# sheet3_nRF52832.net
KiCad netlist of a schematic drawn in Altium Designer
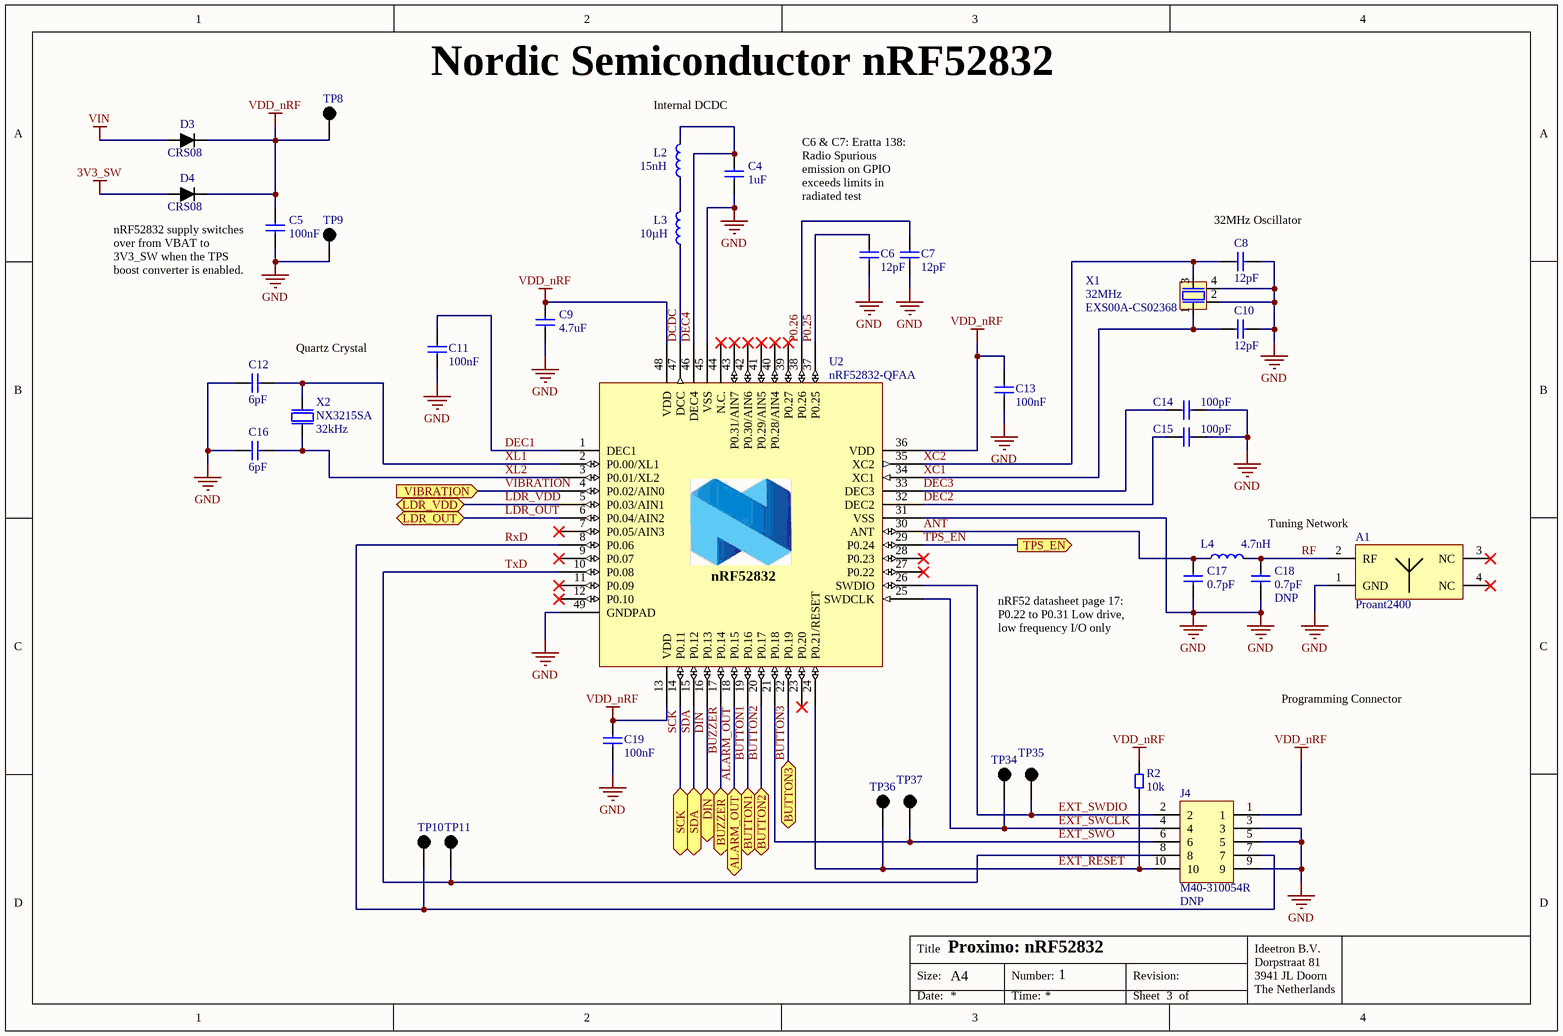
[diagram p0: sheet3_nRF52832.SchDoc]

(export (version "E")
  (design (tool "Eeschema 10.0.6"))
  (components
    (comp (ref "A1")
      (value "Proant2400")
      (footprint "Proant2400")
      (description "Onboard SMD 2400 MHz Antenna for BLE, WLAN/Wifi")
      (fields (field (name "MANUFACTURER") "Proant") (field (name "MANUFACTURER PART NUMBER") "PRO-OB-440"))
      (libsource (lib "Schlib") (part "Proant2400"))
    )
    (comp (ref "C4")
      (value "1uF")
      (footprint "CAP0603_GR18_MURATA")
      (description "Capacitor 1uF X5R 0603 Murata")
      (fields
        (field (name "MANUFACTURER") "Murata")
        (field (name "MANUFACTURER PART NUMBER") "GRM188R61E105KA12D")
      )
      (libsource (lib "Schlib") (part "CAP_0603_1uF"))
    )
    (comp (ref "C5")
      (value "100nF")
      (footprint "CAP0603_GCx18_MURATA")
      (description "Capacitor 0603 100nF")
      (fields
        (field (name "MANUFACTURER") "Murata")
        (field (name "MANUFACTURER PART NUMBER") "GCJ188R71C104KA01D")
      )
      (libsource (lib "Schlib") (part "CAP_0603_100nF"))
    )
    (comp (ref "C6")
      (value "12pF")
      (footprint "CAP0402_GCx15_Murata")
      (description "Capacitor NP0 0402")
      (fields
        (field (name "MANUFACTURER") "Murata")
        (field (name "MANUFACTURER PART NUMBER") "GCM1555C1H120JA16D")
      )
      (libsource (lib "Schlib") (part "CAP_0402_12pF"))
    )
    (comp (ref "C7")
      (value "12pF")
      (footprint "CAP0402_GCx15_Murata")
      (description "Capacitor NP0 0402")
      (fields
        (field (name "MANUFACTURER") "Murata")
        (field (name "MANUFACTURER PART NUMBER") "GCM1555C1H120JA16D")
      )
      (libsource (lib "Schlib") (part "CAP_0402_12pF"))
    )
    (comp (ref "C8")
      (value "12pF")
      (footprint "CAP0402_GCx15_Murata")
      (description "Capacitor NP0 0402")
      (fields
        (field (name "MANUFACTURER") "Murata")
        (field (name "MANUFACTURER PART NUMBER") "GCM1555C1H120JA16D")
      )
      (libsource (lib "Schlib") (part "CAP_0402_12pF"))
    )
    (comp (ref "C9")
      (value "4.7uF")
      (footprint "CAP0603_GR18_MURATA")
      (description "Capacitor X5R 0603 Murata")
      (fields
        (field (name "MANUFACTURER") "Murata")
        (field (name "MANUFACTURER PART NUMBER") "GRM188R60J475KE19D")
      )
      (libsource (lib "Schlib") (part "CAP_0603_4u7"))
    )
    (comp (ref "C10")
      (value "12pF")
      (footprint "CAP0402_GCx15_Murata")
      (description "Capacitor NP0 0402")
      (fields
        (field (name "MANUFACTURER") "Murata")
        (field (name "MANUFACTURER PART NUMBER") "GCM1555C1H120JA16D")
      )
      (libsource (lib "Schlib") (part "CAP_0402_12pF"))
    )
    (comp (ref "C11")
      (value "100nF")
      (footprint "CAP0603_GCx18_MURATA")
      (description "Capacitor 0603 100nF")
      (fields
        (field (name "MANUFACTURER") "Murata")
        (field (name "MANUFACTURER PART NUMBER") "GCJ188R71C104KA01D")
      )
      (libsource (lib "Schlib") (part "CAP_0603_100nF"))
    )
    (comp (ref "C12")
      (value "6pF")
      (footprint "CAP0603_GCx18_MURATA")
      (description "Capacitor NP0 0603 50V")
      (fields (field (name "PART NUMBER") "GCM1885C1H6R0CA16D") (field (name "MANUFACTURER") "Murata"))
      (libsource (lib "Schlib") (part "CAP_0603_6pF"))
    )
    (comp (ref "C13")
      (value "100nF")
      (footprint "CAP0603_GCx18_MURATA")
      (description "Capacitor 0603 100nF")
      (fields
        (field (name "MANUFACTURER") "Murata")
        (field (name "MANUFACTURER PART NUMBER") "GCJ188R71C104KA01D")
      )
      (libsource (lib "Schlib") (part "CAP_0603_100nF"))
    )
    (comp (ref "C14")
      (value "100pF")
      (footprint "CAP0603_GCx18_MURATA")
      (description "Capacitor 100pF 0603 NP0")
      (fields
        (field (name "MANUFACTURER") "Murata")
        (field (name "MANUFACTURER PART NUMBER") "GCM1885C1H101JA16D")
      )
      (libsource (lib "Schlib") (part "CAP_0603_100pF"))
    )
    (comp (ref "C15")
      (value "100pF")
      (footprint "CAP0603_GCx18_MURATA")
      (description "Capacitor 100pF 0603 NP0")
      (fields
        (field (name "MANUFACTURER") "Murata")
        (field (name "MANUFACTURER PART NUMBER") "GCM1885C1H101JA16D")
      )
      (libsource (lib "Schlib") (part "CAP_0603_100pF"))
    )
    (comp (ref "C16")
      (value "6pF")
      (footprint "CAP0603_GCx18_MURATA")
      (description "Capacitor NP0 0603 50V")
      (fields (field (name "PART NUMBER") "GCM1885C1H6R0CA16D") (field (name "MANUFACTURER") "Murata"))
      (libsource (lib "Schlib") (part "CAP_0603_6pF"))
    )
    (comp (ref "C17")
      (value "0.7pF")
      (footprint "CAP0402 Johansen Technology")
      (description "Capacitor 0.7pF 0402")
      (fields
        (field (name "MANUFACTURER") "Johansen Technology")
        (field (name "MANUFACTURER PART NUMBER") "500R07S0R7AV4T")
      )
      (libsource (lib "Schlib") (part "CAP_0402_0p7F"))
    )
    (comp (ref "C18")
      (value "0.7pF")
      (footprint "CAP0402 Johansen Technology")
      (description "Capacitor 0.7pF 0402")
      (fields (field (name "MANUFACTURER PART NUMBER") "500R07S0R7AV4T") (field (name "REMARK") "DNP"))
      (libsource (lib "Schlib") (part "CAP_0402_0p7F"))
    )
    (comp (ref "C19")
      (value "100nF")
      (footprint "CAP0603_GCx18_MURATA")
      (description "Capacitor 0603 100nF")
      (fields
        (field (name "MANUFACTURER") "Murata")
        (field (name "MANUFACTURER PART NUMBER") "GCJ188R71C104KA01D")
      )
      (libsource (lib "Schlib") (part "CAP_0603_100nF"))
    )
    (comp (ref "D3")
      (value "CRS08")
      (footprint "SOD-123F")
      (description "CRS08 Schottky Diode")
      (fields (field (name "MANUFACTURER") "Tohsiba"))
      (libsource (lib "Schlib") (part "CRS08 Schottky Diode"))
    )
    (comp (ref "D4")
      (value "CRS08")
      (footprint "SOD-123F")
      (description "CRS08 Schottky Diode")
      (fields (field (name "MANUFACTURER") "Tohsiba"))
      (libsource (lib "Schlib") (part "CRS08 Schottky Diode"))
    )
    (comp (ref "J4")
      (value "M40-310054R")
      (footprint "Harwin connector")
      (description "Harwin connector 2Rows x 6 contacts M40-3100545R")
      (fields (field (name "MANUFACTURER") "Harwin") (field (name "REMARK") "DNP"))
      (libsource (lib "Schlib") (part "Harwin Connector"))
    )
    (comp (ref "L2")
      (value "15nH")
      (footprint "WE-MK_0402A")
      (description "WE-MK Multilayer Ceramic SMD Inductor, size 0402A, 15nH")
      (fields
        (field (name "PARTNUMBER") "744784115A")
        (field (name "MANUFACTURER") "Wurth Elektronik")
        (field (name "PUBLISHER") "Wurth Elektronik")
      )
      (libsource (lib "Schlib") (part "WE-MK, 744784115A"))
    )
    (comp (ref "L3")
      (value "10µH")
      (footprint "74479777xxx_0805")
      (description "WE-PMI Power Multilayer Inductor, L= 10.0µH")
      (fields
        (field (name "PARTNO") "74479777310A")
        (field (name "MANUFACTURER") "Wurth Elektronik")
        (field (name "CREATED BY") "Baojun Chen")
      )
      (libsource (lib "Schlib") (part "WE-PMI 0805, 74479777310A"))
    )
    (comp (ref "L4")
      (value "4.7nH")
      (footprint "IND RF 0402HP-4N7XJLU")
      (description "High frequency chip inductor 0402 Coil Craft")
      (fields
        (field (name "MANUFACTURER") "Coilcraft")
        (field (name "MANUFACTURER PART NUMBER") "500R07S0R7AV4T")
      )
      (libsource (lib "Schlib") (part "IND_0402 Coilcraft 500R07S0R7AV4T"))
    )
    (comp (ref "R2")
      (value "10k")
      (footprint "RES0603VISHAY")
      (description "SMD Resistor 10k 0603")
      (fields
        (field (name "MANUFACTURER") "Vishay")
        (field (name "MANUFACTURER PART NUMBER") "CRCW060310K0FKTABC")
      )
      (libsource (lib "Schlib") (part "Resistor_10k"))
    )
    (comp (ref "TP8")
      (value "testpad")
      (footprint "TestPad")
      (description "Signal probe pad")
      (libsource (lib "Schlib") (part "TestPad"))
    )
    (comp (ref "TP9")
      (value "testpad")
      (footprint "TestPad")
      (description "Signal probe pad")
      (libsource (lib "Schlib") (part "TestPad"))
    )
    (comp (ref "TP10")
      (value "testpad")
      (footprint "TestPad")
      (description "Signal probe pad")
      (libsource (lib "Schlib") (part "TestPad"))
    )
    (comp (ref "TP11")
      (value "testpad")
      (footprint "TestPad")
      (description "Signal probe pad")
      (libsource (lib "Schlib") (part "TestPad"))
    )
    (comp (ref "TP34")
      (value "testpad")
      (footprint "TestPad")
      (description "Signal probe pad")
      (libsource (lib "Schlib") (part "TestPad"))
    )
    (comp (ref "TP35")
      (value "testpad")
      (footprint "TestPad")
      (description "Signal probe pad")
      (libsource (lib "Schlib") (part "TestPad"))
    )
    (comp (ref "TP36")
      (value "testpad")
      (footprint "TestPad")
      (description "Signal probe pad")
      (libsource (lib "Schlib") (part "TestPad"))
    )
    (comp (ref "TP37")
      (value "testpad")
      (footprint "TestPad")
      (description "Signal probe pad")
      (libsource (lib "Schlib") (part "TestPad"))
    )
    (comp (ref "U2")
      (value "nRF52832-QFAA")
      (footprint "QFN40P600X600X90-48N")
      (description "Multi-protocol Bluetooth Low Energy, ANT and 2.4GHz proprietary system-on-chip")
      (fields
        (field (name "MANUFACTURER") "Nordic Semiconductor")
        (field (name "PUBLISHER") "Nordic Semiconductor")
      )
      (libsource (lib "Schlib") (part "nRF52832_QFAA"))
    )
    (comp (ref "X1")
      (value "EXS00A-CS02368")
      (footprint "NDK-32MHz-XTAL")
      (description "NDK  NX3225SA 32MHz Oscillator")
      (fields
        (field (name "MANUFACTURER") "NDK")
        (field (name "MANUFACTURER PART NUMBER") "NX3225SA")
        (field (name "FREQUENCY") "32MHz")
      )
      (libsource (lib "Schlib") (part "NDK_32MHZ_OCILLATOR"))
    )
    (comp (ref "X2")
      (value "NX3215SA")
      (footprint "XTAL_3215")
      (description "XTAL SMD 3215, 32.768kHz, Cl=9pF, Total Tol: ±50ppm")
      (fields
        (field (name "PART NUMBER") "XTAL_FC-135 32.768k")
        (field (name "MANUFACTURER") "NDK")
        (field (name "FREQUENCY") "32kHz")
      )
      (libsource (lib "Schlib") (part "NDK_32kHz"))
    )
  )
  (nets
    (net (code "1") (name "/ALARM_OUT") (class "Default")
      (node (ref "U2") (pin "18") (pinfunction "P0.15_18") (pintype "bidirectional"))
    )
    (net (code "2") (name "/ANT") (class "Default")
      (node (ref "C17") (pin "2") (pinfunction "2_2") (pintype "passive"))
      (node (ref "L4") (pin "1") (pinfunction "1_1") (pintype "passive"))
      (node (ref "U2") (pin "30") (pinfunction "ANT_30") (pintype "bidirectional"))
    )
    (net (code "3") (name "/BUTTON1") (class "Default")
      (node (ref "U2") (pin "19") (pinfunction "P0.16_19") (pintype "bidirectional"))
    )
    (net (code "4") (name "/BUTTON2") (class "Default")
      (node (ref "U2") (pin "20") (pinfunction "P0.17_20") (pintype "bidirectional"))
    )
    (net (code "5") (name "/BUTTON3") (class "Default")
      (node (ref "U2") (pin "22") (pinfunction "P0.19_22") (pintype "bidirectional"))
    )
    (net (code "6") (name "/BUZZER") (class "Default")
      (node (ref "U2") (pin "17") (pinfunction "P0.14_17") (pintype "bidirectional"))
    )
    (net (code "7") (name "/DCDC") (class "Default")
      (node (ref "L3") (pin "1") (pinfunction "1_1") (pintype "passive"))
      (node (ref "U2") (pin "47") (pinfunction "DCC_47") (pintype "output"))
    )
    (net (code "8") (name "/DEC1") (class "Default")
      (node (ref "C11") (pin "2") (pinfunction "2_2") (pintype "passive"))
      (node (ref "U2") (pin "1") (pinfunction "DEC1_1") (pintype "power_in"))
    )
    (net (code "9") (name "/DEC2") (class "Default")
      (node (ref "C15") (pin "1") (pinfunction "1_1") (pintype "passive"))
      (node (ref "U2") (pin "32") (pinfunction "DEC2_32") (pintype "power_in"))
    )
    (net (code "10") (name "/DEC3") (class "Default")
      (node (ref "C14") (pin "1") (pinfunction "1_1") (pintype "passive"))
      (node (ref "U2") (pin "33") (pinfunction "DEC3_33") (pintype "power_in"))
    )
    (net (code "11") (name "/DEC4") (class "Default")
      (node (ref "C4") (pin "2") (pinfunction "2_2") (pintype "passive"))
      (node (ref "L2") (pin "2") (pinfunction "2_2") (pintype "passive"))
      (node (ref "U2") (pin "46") (pinfunction "DEC4_46") (pintype "power_in"))
    )
    (net (code "12") (name "/DIN") (class "Default")
      (node (ref "U2") (pin "16") (pinfunction "P0.13_16") (pintype "bidirectional"))
    )
    (net (code "13") (name "/EXT_RESET") (class "Default")
      (node (ref "J4") (pin "10") (pinfunction "10_10") (pintype "passive"))
      (node (ref "R2") (pin "1") (pinfunction "1_1") (pintype "passive"))
      (node (ref "TP36") (pin "1") (pinfunction "1_1") (pintype "passive"))
      (node (ref "U2") (pin "24") (pinfunction "P0.21/RESET_24") (pintype "bidirectional"))
    )
    (net (code "14") (name "/EXT_SWCLK") (class "Default")
      (node (ref "J4") (pin "4") (pinfunction "4_4") (pintype "passive"))
      (node (ref "TP34") (pin "1") (pinfunction "1_1") (pintype "passive"))
      (node (ref "U2") (pin "25") (pinfunction "SWDCLK_25") (pintype "input"))
    )
    (net (code "15") (name "/EXT_SWDIO") (class "Default")
      (node (ref "J4") (pin "2") (pinfunction "2_2") (pintype "passive"))
      (node (ref "TP35") (pin "1") (pinfunction "1_1") (pintype "passive"))
      (node (ref "U2") (pin "26") (pinfunction "SWDIO_26") (pintype "bidirectional"))
    )
    (net (code "16") (name "/EXT_SWO") (class "Default")
      (node (ref "J4") (pin "6") (pinfunction "6_6") (pintype "passive"))
      (node (ref "TP37") (pin "1") (pinfunction "1_1") (pintype "passive"))
      (node (ref "U2") (pin "21") (pinfunction "P0.18_21") (pintype "bidirectional"))
    )
    (net (code "17") (name "/LDR_OUT") (class "Default")
      (node (ref "U2") (pin "6") (pinfunction "P0.04/AIN2_6") (pintype "bidirectional"))
    )
    (net (code "18") (name "/LDR_VDD") (class "Default")
      (node (ref "U2") (pin "5") (pinfunction "P0.03/AIN1_5") (pintype "bidirectional"))
    )
    (net (code "19") (name "/P0.25") (class "Default")
      (node (ref "C6") (pin "2") (pinfunction "2_2") (pintype "passive"))
      (node (ref "U2") (pin "37") (pinfunction "P0.25_37") (pintype "bidirectional"))
    )
    (net (code "20") (name "/P0.26") (class "Default")
      (node (ref "C7") (pin "2") (pinfunction "2_2") (pintype "passive"))
      (node (ref "U2") (pin "38") (pinfunction "P0.26_38") (pintype "bidirectional"))
    )
    (net (code "21") (name "/RF") (class "Default")
      (node (ref "A1") (pin "2") (pinfunction "RF_2") (pintype "passive"))
      (node (ref "C18") (pin "2") (pinfunction "2_2") (pintype "passive"))
      (node (ref "L4") (pin "2") (pinfunction "2_2") (pintype "passive"))
    )
    (net (code "22") (name "/RxD") (class "Default")
      (node (ref "J4") (pin "7") (pinfunction "7_7") (pintype "passive"))
      (node (ref "TP10") (pin "1") (pinfunction "1_1") (pintype "passive"))
      (node (ref "U2") (pin "8") (pinfunction "P0.06_8") (pintype "bidirectional"))
    )
    (net (code "23") (name "/SCK") (class "Default")
      (node (ref "U2") (pin "14") (pinfunction "P0.11_14") (pintype "bidirectional"))
    )
    (net (code "24") (name "/SDA") (class "Default")
      (node (ref "U2") (pin "15") (pinfunction "P0.12_15") (pintype "bidirectional"))
    )
    (net (code "25") (name "/TPS_EN") (class "Default")
      (node (ref "U2") (pin "29") (pinfunction "P0.24_29") (pintype "bidirectional"))
    )
    (net (code "26") (name "/TxD") (class "Default")
      (node (ref "J4") (pin "8") (pinfunction "8_8") (pintype "passive"))
      (node (ref "TP11") (pin "1") (pinfunction "1_1") (pintype "passive"))
      (node (ref "U2") (pin "10") (pinfunction "P0.08_10") (pintype "bidirectional"))
    )
    (net (code "27") (name "/VIBRATION") (class "Default")
      (node (ref "U2") (pin "4") (pinfunction "P0.02/AIN0_4") (pintype "bidirectional"))
    )
    (net (code "28") (name "/XC1") (class "Default")
      (node (ref "C10") (pin "2") (pinfunction "2_2") (pintype "passive"))
      (node (ref "U2") (pin "34") (pinfunction "XC1_34") (pintype "input"))
      (node (ref "X1") (pin "1") (pinfunction "inp_1") (pintype "passive"))
    )
    (net (code "29") (name "/XC2") (class "Default")
      (node (ref "C8") (pin "2") (pinfunction "2_2") (pintype "passive"))
      (node (ref "U2") (pin "35") (pinfunction "XC2_35") (pintype "output"))
      (node (ref "X1") (pin "3") (pinfunction "out_3") (pintype "passive"))
    )
    (net (code "30") (name "/XL1") (class "Default")
      (node (ref "C12") (pin "2") (pinfunction "2_2") (pintype "passive"))
      (node (ref "U2") (pin "2") (pinfunction "P0.00/XL1_2") (pintype "bidirectional"))
      (node (ref "X2") (pin "2") (pinfunction "out_2") (pintype "passive"))
    )
    (net (code "31") (name "/XL2") (class "Default")
      (node (ref "C16") (pin "2") (pinfunction "2_2") (pintype "passive"))
      (node (ref "U2") (pin "3") (pinfunction "P0.01/XL2_3") (pintype "bidirectional"))
      (node (ref "X2") (pin "1") (pinfunction "inp_1") (pintype "passive"))
    )
    (net (code "32") (name "3V3_SW") (class "Default")
      (node (ref "D4") (pin "A") (pinfunction "A_A") (pintype "passive"))
    )
    (net (code "33") (name "GND") (class "Default")
      (node (ref "A1") (pin "1") (pinfunction "GND_1") (pintype "passive"))
      (node (ref "C10") (pin "1") (pinfunction "1_1") (pintype "passive"))
      (node (ref "C11") (pin "1") (pinfunction "1_1") (pintype "passive"))
      (node (ref "C12") (pin "1") (pinfunction "1_1") (pintype "passive"))
      (node (ref "C13") (pin "1") (pinfunction "1_1") (pintype "passive"))
      (node (ref "C14") (pin "2") (pinfunction "2_2") (pintype "passive"))
      (node (ref "C15") (pin "2") (pinfunction "2_2") (pintype "passive"))
      (node (ref "C16") (pin "1") (pinfunction "1_1") (pintype "passive"))
      (node (ref "C17") (pin "1") (pinfunction "1_1") (pintype "passive"))
      (node (ref "C18") (pin "1") (pinfunction "1_1") (pintype "passive"))
      (node (ref "C19") (pin "1") (pinfunction "1_1") (pintype "passive"))
      (node (ref "C4") (pin "1") (pinfunction "1_1") (pintype "passive"))
      (node (ref "C5") (pin "1") (pinfunction "1_1") (pintype "passive"))
      (node (ref "C6") (pin "1") (pinfunction "1_1") (pintype "passive"))
      (node (ref "C7") (pin "1") (pinfunction "1_1") (pintype "passive"))
      (node (ref "C8") (pin "1") (pinfunction "1_1") (pintype "passive"))
      (node (ref "C9") (pin "1") (pinfunction "1_1") (pintype "passive"))
      (node (ref "J4") (pin "3") (pinfunction "3_3") (pintype "passive"))
      (node (ref "J4") (pin "5") (pinfunction "5_5") (pintype "passive"))
      (node (ref "J4") (pin "9") (pinfunction "9_9") (pintype "passive"))
      (node (ref "TP9") (pin "1") (pinfunction "1_1") (pintype "passive"))
      (node (ref "U2") (pin "31") (pinfunction "VSS_31") (pintype "power_in"))
      (node (ref "U2") (pin "45") (pinfunction "VSS_45") (pintype "power_in"))
      (node (ref "U2") (pin "49") (pinfunction "GNDPAD_49") (pintype "power_in"))
      (node (ref "X1") (pin "2") (pinfunction "GND_2") (pintype "passive"))
      (node (ref "X1") (pin "4") (pinfunction "GND_4") (pintype "passive"))
    )
    (net (code "34") (name "Net-(L2-Pad1)") (class "Default")
      (node (ref "L2") (pin "1") (pinfunction "1_1") (pintype "passive"))
      (node (ref "L3") (pin "2") (pinfunction "2_2") (pintype "passive"))
    )
    (net (code "35") (name "VDD_nRF") (class "Default")
      (node (ref "C13") (pin "2") (pinfunction "2_2") (pintype "passive"))
      (node (ref "C19") (pin "2") (pinfunction "2_2") (pintype "passive"))
      (node (ref "C5") (pin "2") (pinfunction "2_2") (pintype "passive"))
      (node (ref "C9") (pin "2") (pinfunction "2_2") (pintype "passive"))
      (node (ref "D3") (pin "C") (pinfunction "C_C") (pintype "passive"))
      (node (ref "D4") (pin "C") (pinfunction "C_C") (pintype "passive"))
      (node (ref "J4") (pin "1") (pinfunction "1_1") (pintype "passive"))
      (node (ref "R2") (pin "2") (pinfunction "2_2") (pintype "passive"))
      (node (ref "TP8") (pin "1") (pinfunction "1_1") (pintype "passive"))
      (node (ref "U2") (pin "13") (pinfunction "VDD_13") (pintype "power_in"))
      (node (ref "U2") (pin "36") (pinfunction "VDD_36") (pintype "power_in"))
      (node (ref "U2") (pin "48") (pinfunction "VDD_48") (pintype "power_in"))
    )
    (net (code "36") (name "VIN") (class "Default")
      (node (ref "D3") (pin "A") (pinfunction "A_A") (pintype "passive"))
    )
    (net (code "37") (name "unconnected-(A1-NC-Pad3)") (class "Default")
      (node (ref "A1") (pin "3") (pinfunction "NC_3") (pintype "passive+no_connect"))
    )
    (net (code "38") (name "unconnected-(A1-NC-Pad4)") (class "Default")
      (node (ref "A1") (pin "4") (pinfunction "NC_4") (pintype "passive+no_connect"))
    )
    (net (code "39") (name "unconnected-(U2-N.C.-Pad44)") (class "Default")
      (node (ref "U2") (pin "44") (pinfunction "N.C._44") (pintype "power_in+no_connect"))
    )
    (net (code "40") (name "unconnected-(U2-P0.05{slash}AIN3-Pad7)") (class "Default")
      (node (ref "U2") (pin "7") (pinfunction "P0.05/AIN3_7") (pintype "bidirectional+no_connect"))
    )
    (net (code "41") (name "unconnected-(U2-P0.07-Pad9)") (class "Default")
      (node (ref "U2") (pin "9") (pinfunction "P0.07_9") (pintype "bidirectional+no_connect"))
    )
    (net (code "42") (name "unconnected-(U2-P0.09-Pad11)") (class "Default")
      (node (ref "U2") (pin "11") (pinfunction "P0.09_11") (pintype "bidirectional+no_connect"))
    )
    (net (code "43") (name "unconnected-(U2-P0.10-Pad12)") (class "Default")
      (node (ref "U2") (pin "12") (pinfunction "P0.10_12") (pintype "bidirectional+no_connect"))
    )
    (net (code "44") (name "unconnected-(U2-P0.20-Pad23)") (class "Default")
      (node (ref "U2") (pin "23") (pinfunction "P0.20_23") (pintype "bidirectional+no_connect"))
    )
    (net (code "45") (name "unconnected-(U2-P0.22-Pad27)") (class "Default")
      (node (ref "U2") (pin "27") (pinfunction "P0.22_27") (pintype "bidirectional+no_connect"))
    )
    (net (code "46") (name "unconnected-(U2-P0.23-Pad28)") (class "Default")
      (node (ref "U2") (pin "28") (pinfunction "P0.23_28") (pintype "bidirectional+no_connect"))
    )
    (net (code "47") (name "unconnected-(U2-P0.27-Pad39)") (class "Default")
      (node (ref "U2") (pin "39") (pinfunction "P0.27_39") (pintype "bidirectional+no_connect"))
    )
    (net (code "48") (name "unconnected-(U2-P0.28{slash}AIN4-Pad40)") (class "Default")
      (node (ref "U2") (pin "40") (pinfunction "P0.28/AIN4_40") (pintype "bidirectional+no_connect"))
    )
    (net (code "49") (name "unconnected-(U2-P0.29{slash}AIN5-Pad41)") (class "Default")
      (node (ref "U2") (pin "41") (pinfunction "P0.29/AIN5_41") (pintype "bidirectional+no_connect"))
    )
    (net (code "50") (name "unconnected-(U2-P0.30{slash}AIN6-Pad42)") (class "Default")
      (node (ref "U2") (pin "42") (pinfunction "P0.30/AIN6_42") (pintype "bidirectional+no_connect"))
    )
    (net (code "51") (name "unconnected-(U2-P0.31{slash}AIN7-Pad43)") (class "Default")
      (node (ref "U2") (pin "43") (pinfunction "P0.31/AIN7_43") (pintype "bidirectional+no_connect"))
    )
  )
)
